# Harvester_RF.net
KiCad netlist of a schematic drawn in Altium Designer
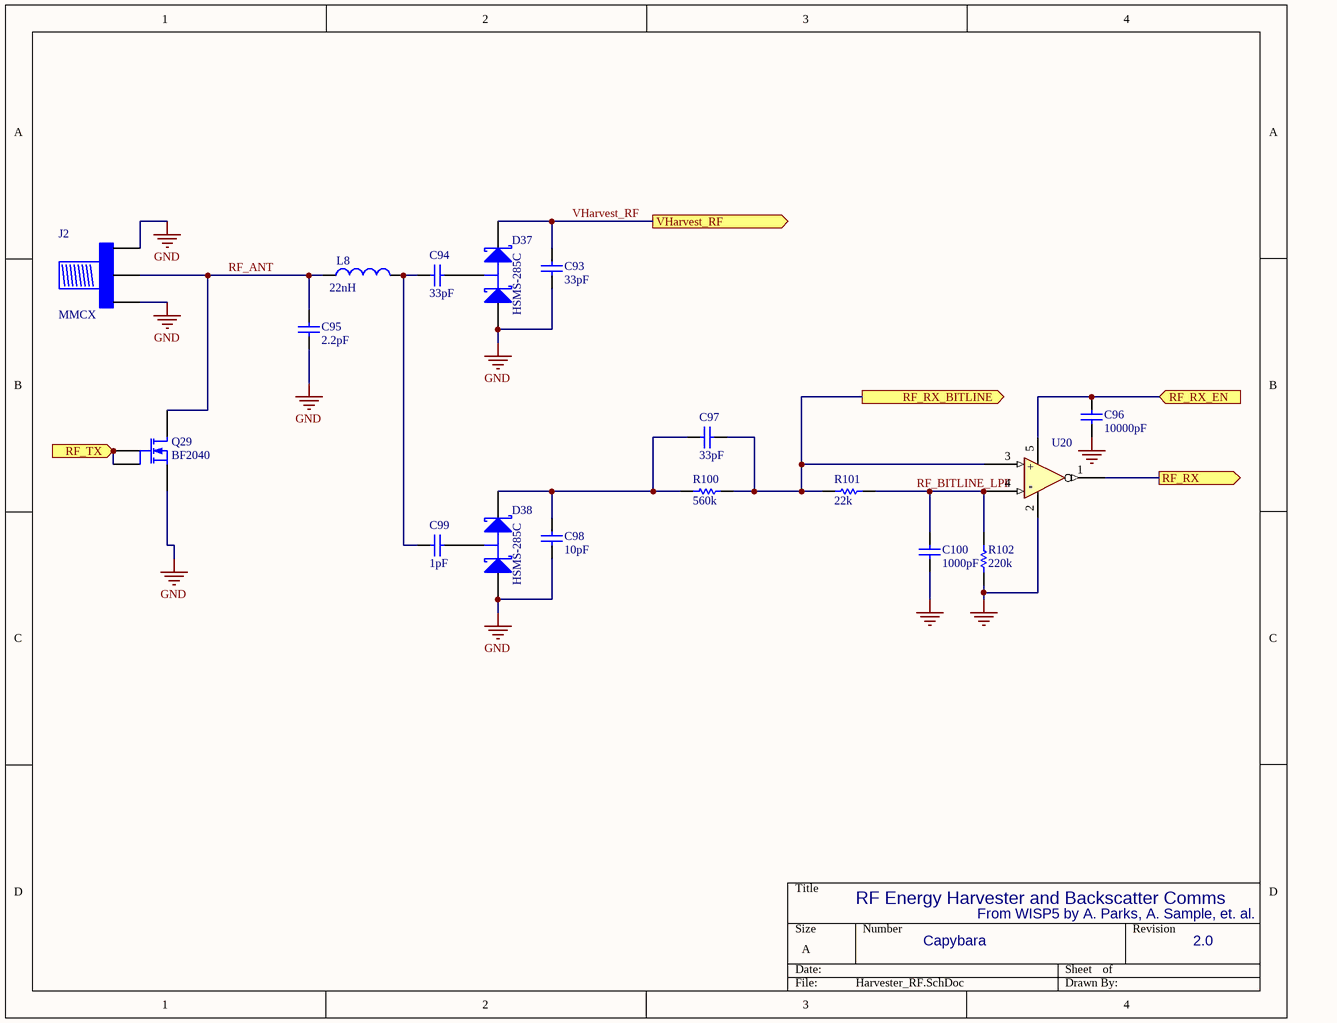
[diagram p0: Harvester_RF.SchDoc]

(export (version "E")
  (design (tool "Eeschema 10.0.6"))
  (components
    (comp (ref "C93")
      (value "33pF")
      (footprint "0402")
      (description "Ceramic Capacitor (Surface Mount)")
      (fields (field (name "DIGI-KEY PART NUMBER") "712-1298-1-ND") (field (name "MANUFACTURER") "Johanson"))
      (libsource (lib "WISP_AD10") (part "Cap"))
    )
    (comp (ref "C94")
      (value "33pF")
      (footprint "0402")
      (description "Ceramic Capacitor (Surface Mount)")
      (fields (field (name "DIGI-KEY PART NUMBER") "712-1298-1-ND") (field (name "MANUFACTURER") "Johanson"))
      (libsource (lib "WISP_AD10") (part "Cap"))
    )
    (comp (ref "C95")
      (value "2.2pF")
      (footprint "0402")
      (description "Ceramic Capacitor (Surface Mount)")
      (fields (field (name "DIGI-KEY PART NUMBER") "712-1289-1-ND") (field (name "MANUFACTURER") "Johanson"))
      (libsource (lib "WISP_AD10") (part "Cap"))
    )
    (comp (ref "C96")
      (value "10000pF")
      (footprint "0402")
      (description "Ceramic Capacitor (Surface Mount)")
      (fields
        (field (name "MANUFACTURER") "Murata Electronics North America")
        (field (name "MANUFACTURER PART NUMBER") "GRM188R61A105KA61D")
      )
      (libsource (lib "WISP_AD10") (part "Cap"))
    )
    (comp (ref "C97")
      (value "33pF")
      (footprint "0402")
      (description "Ceramic Capacitor (Surface Mount)")
      (fields (field (name "DIGI-KEY PART NUMBER") "712-1298-1-ND") (field (name "MANUFACTURER") "Johanson"))
      (libsource (lib "WISP_AD10") (part "Cap"))
    )
    (comp (ref "C98")
      (value "10pF")
      (footprint "0402")
      (description "Ceramic Capacitor (Surface Mount)")
      (fields (field (name "DIGI-KEY PART NUMBER") "712-1253-1-ND") (field (name "MANUFACTURER") "Johanson"))
      (libsource (lib "WISP_AD10") (part "Cap"))
    )
    (comp (ref "C99")
      (value "1pF")
      (footprint "0402")
      (description "Ceramic Capacitor (Surface Mount)")
      (fields
        (field (name "DIGI-KEY PART NUMBER") "712-1266-1-ND")
        (field (name "MANUFACTURER") "Murata Electronics")
      )
      (libsource (lib "WISP_AD10") (part "Cap"))
    )
    (comp (ref "C100")
      (value "1000pF")
      (footprint "0402")
      (description "Ceramic Capacitor (Surface Mount)")
      (fields
        (field (name "DIGI-KEY PART NUMBER") "490-3244-1-ND")
        (field (name "MANUFACTURER") "Generic Ceramic Chip Cap (TBD)")
      )
      (libsource (lib "WISP_AD10") (part "Cap"))
    )
    (comp (ref "D37")
      (value "HSMS-285C")
      (footprint "SOT-323, HSMS-285C")
      (description "Agilent Schottky Diode, Two in Series, Small Package SOT-323")
      (fields
        (field (name "DIGI-KEY PART NUMBER") "516-2558-ND")
        (field (name "MANUFACTURER") "Avago Technologies US Inc.")
      )
      (libsource (lib "WISP_AD10") (part "HSMS-285C"))
    )
    (comp (ref "D38")
      (value "HSMS-285C")
      (footprint "SOT-323, HSMS-285C")
      (description "Agilent Schottky Diode, Two in Series, Small Package SOT-323")
      (fields
        (field (name "DIGI-KEY PART NUMBER") "516-2558-ND")
        (field (name "MANUFACTURER") "Avago Technologies US Inc.")
      )
      (libsource (lib "WISP_AD10") (part "HSMS-285C"))
    )
    (comp (ref "J2")
      (value "MMCX")
      (footprint "MMCX-TH")
      (description "MMCX RF Connector")
      (fields
        (field (name "DIGI-KEY PART NUMBER") "WM5552-ND")
        (field (name "MANUFACTURER PART NUMBER") "0734151001")
      )
      (libsource (lib "Sprite") (part "MMCX"))
    )
    (comp (ref "L8")
      (value "22nH")
      (footprint "0402")
      (description "Inductor (Surface Mount)")
      (fields
        (field (name "MANUFACTURER") "Coilcraft (http://www.coilcraft.com/0402cs.cfm)")
        (field (name "MANUFACTURER PART NUMBER") "0402CS-22NX_LU")
      )
      (libsource (lib "WISP_AD10") (part "Ind"))
    )
    (comp (ref "Q29")
      (value "BF2040")
      (footprint "SOT-143")
      (description "N-Channel RF MOSFET 1GHz, 40mA")
      (fields
        (field (name "DIGI-KEY PART NUMBER") "BF2040E6814HTSA1CT-ND")
        (field (name "MANUFACTURER PART NUMBER") "BF2040E6814HTSA1")
      )
      (libsource (lib "DRP_Basic_2014") (part "BF2040"))
    )
    (comp (ref "R100")
      (value "560k")
      (footprint "0402")
      (description "Chip Resistor (Surface Mount)")
      (fields
        (field (name "MANUFACTURER") "Panasonic")
        (field (name "MANUFACTURER PART NUMBER") "ERJ-2RKF5603X")
      )
      (libsource (lib "WISP_AD10") (part "Res"))
    )
    (comp (ref "R101")
      (value "22k")
      (footprint "0402")
      (description "Chip Resistor (Surface Mount)")
      (fields
        (field (name "MANUFACTURER") "Panasonic")
        (field (name "MANUFACTURER PART NUMBER") "ERJ-2RKF2202X")
      )
      (libsource (lib "WISP_AD10") (part "Res"))
    )
    (comp (ref "R102")
      (value "220k")
      (footprint "0402")
      (description "Chip Resistor (Surface Mount)")
      (fields
        (field (name "MANUFACTURER") "Panasonic")
        (field (name "MANUFACTURER PART NUMBER") "ERJ-2RKF2203X")
      )
      (libsource (lib "WISP_AD10") (part "Res"))
    )
    (comp (ref "U20")
      (value "Comparator")
      (footprint "SC70-5")
      (description "Comparator: On Semi 10uA Comparator")
      (fields
        (field (name "DIGI-KEY PART NUMBER") "NCS2200SQ2T2GOSCT-ND")
        (field (name "MANUFACTURER") "ON Semiconductor")
      )
      (libsource (lib "WISP_AD10") (part "NCS2200"))
    )
  )
  (nets
    (net (code "1") (name "/RF_ANT") (class "Default")
      (node (ref "C95") (pin "2") (pinfunction "2_2") (pintype "passive"))
      (node (ref "J2") (pin "1") (pinfunction "1_1") (pintype "passive"))
      (node (ref "L8") (pin "1") (pinfunction "1_1") (pintype "passive"))
      (node (ref "Q29") (pin "2") (pinfunction "D_2") (pintype "passive"))
    )
    (net (code "2") (name "/RF_BITLINE_LPF") (class "Default")
      (node (ref "C100") (pin "1") (pinfunction "1_1") (pintype "passive"))
      (node (ref "R101") (pin "1") (pinfunction "1_1") (pintype "passive"))
      (node (ref "R102") (pin "1") (pinfunction "1_1") (pintype "passive"))
      (node (ref "U20") (pin "4") (pinfunction "In-_4") (pintype "input"))
    )
    (net (code "3") (name "/RF_RX") (class "Default")
      (node (ref "U20") (pin "1") (pinfunction "OUT_1") (pintype "output"))
    )
    (net (code "4") (name "/RF_RX_BITLINE") (class "Default")
      (node (ref "C97") (pin "2") (pinfunction "2_2") (pintype "passive"))
      (node (ref "R100") (pin "1") (pinfunction "1_1") (pintype "passive"))
      (node (ref "R101") (pin "2") (pinfunction "2_2") (pintype "passive"))
      (node (ref "U20") (pin "3") (pinfunction "IN+_3") (pintype "input"))
    )
    (net (code "5") (name "/RF_RX_EN") (class "Default")
      (node (ref "C96") (pin "1") (pinfunction "1_1") (pintype "passive"))
      (node (ref "U20") (pin "5") (pinfunction "VDD_5") (pintype "passive"))
    )
    (net (code "6") (name "/RF_TX") (class "Default")
      (node (ref "Q29") (pin "3") (pinfunction "G2_3") (pintype "passive"))
      (node (ref "Q29") (pin "4") (pinfunction "G1_4") (pintype "passive"))
    )
    (net (code "7") (name "/VHarvest_RF") (class "Default")
      (node (ref "C93") (pin "1") (pinfunction "1_1") (pintype "passive"))
      (node (ref "D37") (pin "2") (pinfunction "K_2") (pintype "passive"))
    )
    (net (code "8") (name "GND") (class "Default")
      (node (ref "C100") (pin "2") (pinfunction "2_2") (pintype "passive"))
      (node (ref "C93") (pin "2") (pinfunction "2_2") (pintype "passive"))
      (node (ref "C95") (pin "1") (pinfunction "1_1") (pintype "passive"))
      (node (ref "C96") (pin "2") (pinfunction "2_2") (pintype "passive"))
      (node (ref "C98") (pin "2") (pinfunction "2_2") (pintype "passive"))
      (node (ref "D37") (pin "1") (pinfunction "A_1") (pintype "passive"))
      (node (ref "D38") (pin "1") (pinfunction "A_1") (pintype "passive"))
      (node (ref "J2") (pin "2") (pinfunction "2_2") (pintype "passive"))
      (node (ref "Q29") (pin "1") (pinfunction "S_1") (pintype "passive"))
      (node (ref "R102") (pin "2") (pinfunction "2_2") (pintype "passive"))
      (node (ref "U20") (pin "2") (pinfunction "Gnd_2") (pintype "power_in"))
    )
    (net (code "9") (name "Net-(C94-Pad1)") (class "Default")
      (node (ref "C94") (pin "1") (pinfunction "1_1") (pintype "passive"))
      (node (ref "C99") (pin "1") (pinfunction "1_1") (pintype "passive"))
      (node (ref "L8") (pin "2") (pinfunction "2_2") (pintype "passive"))
    )
    (net (code "10") (name "Net-(D37-C)") (class "Default")
      (node (ref "C94") (pin "2") (pinfunction "2_2") (pintype "passive"))
      (node (ref "D37") (pin "3") (pinfunction "C_3") (pintype "passive"))
    )
    (net (code "11") (name "Net-(D38-C)") (class "Default")
      (node (ref "C99") (pin "2") (pinfunction "2_2") (pintype "passive"))
      (node (ref "D38") (pin "3") (pinfunction "C_3") (pintype "passive"))
    )
    (net (code "12") (name "Net-(D38-K)") (class "Default")
      (node (ref "C97") (pin "1") (pinfunction "1_1") (pintype "passive"))
      (node (ref "C98") (pin "1") (pinfunction "1_1") (pintype "passive"))
      (node (ref "D38") (pin "2") (pinfunction "K_2") (pintype "passive"))
      (node (ref "R100") (pin "2") (pinfunction "2_2") (pintype "passive"))
    )
  )
)
